# d11toy2ccde.net
KiCad netlist of a schematic drawn in EAGLE
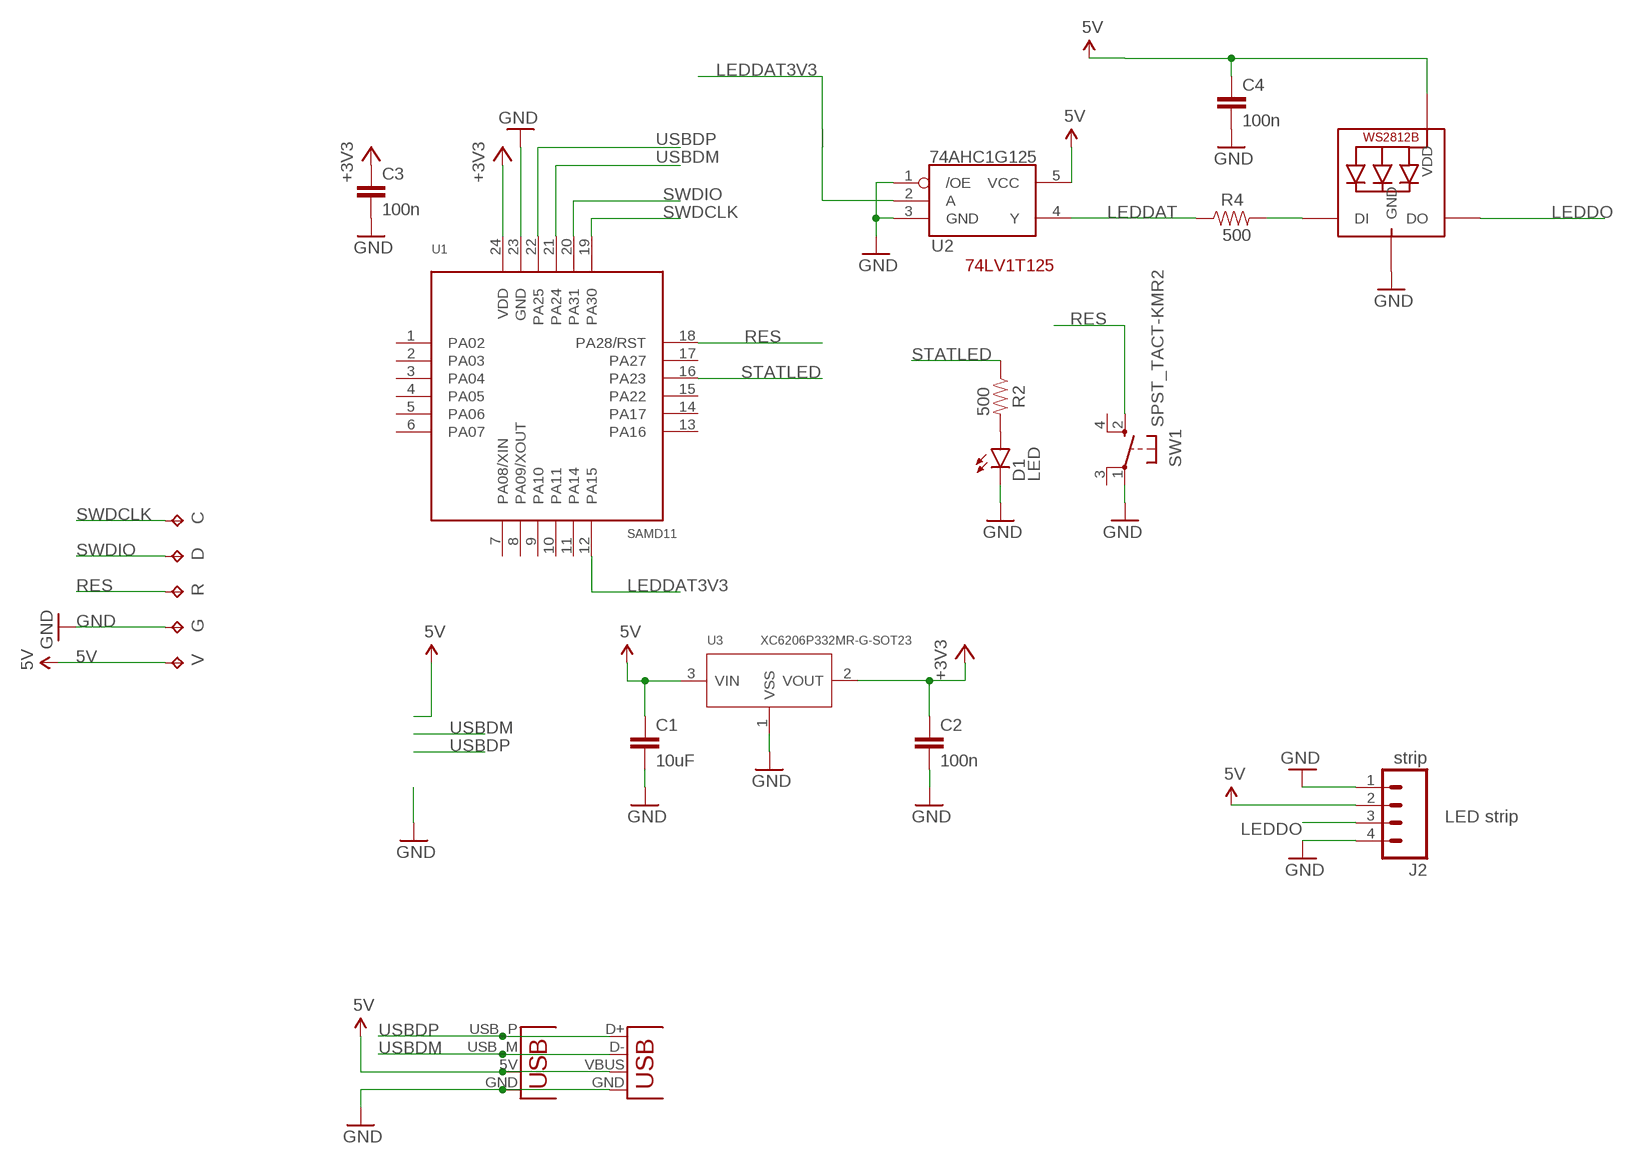
[diagram p0: schematic, sheet 1]

(export (version "E")
  (design (tool "Eeschema 10.0.6"))
  (components
    (comp (ref "C")
      (value "TPTP08R")
      (footprint "eagle-import:TP08R")
      (libsource (lib "eagle-import") (part "TPTP08R"))
    )
    (comp (ref "C1")
      (value "10uF")
      (footprint "eagle-import:0603-CAP")
      (libsource (lib "eagle-import") (part "CAP0603-CAP"))
    )
    (comp (ref "C2")
      (value "100n")
      (footprint "eagle-import:0603-CAP")
      (libsource (lib "eagle-import") (part "CAP0603-CAP"))
    )
    (comp (ref "C3")
      (value "100n")
      (footprint "eagle-import:0603-CAP")
      (libsource (lib "eagle-import") (part "CAP0603-CAP"))
    )
    (comp (ref "C4")
      (value "100n")
      (footprint "eagle-import:0603-CAP")
      (libsource (lib "eagle-import") (part "CAP0603-CAP"))
    )
    (comp (ref "D")
      (value "TPTP08R")
      (footprint "eagle-import:TP08R")
      (libsource (lib "eagle-import") (part "TPTP08R"))
    )
    (comp (ref "D1")
      (value "LED")
      (footprint "eagle-import:LED-0603")
      (libsource (lib "eagle-import") (part "LED0603"))
    )
    (comp (ref "G")
      (value "TPTP08R")
      (footprint "eagle-import:TP08R")
      (libsource (lib "eagle-import") (part "TPTP08R"))
    )
    (comp (ref "J2")
      (value "strip")
      (footprint "eagle-import:1X04_NO_SILK_ALL_ROUND")
      (libsource (lib "eagle-import") (part "M04NO_SILK_ALL_ROUND"))
    )
    (comp (ref "JP1")
      (value "USBPCB")
      (footprint "eagle-import:USB-A-PCB")
      (libsource (lib "eagle-import") (part "USBPCB"))
    )
    (comp (ref "JP3")
      (value "USB-MICROB")
      (footprint "eagle-import:USB-MICROB")
      (libsource (lib "eagle-import") (part "USB-MICROB"))
    )
    (comp (ref "LED1")
      (value "WS2812B5050")
      (footprint "eagle-import:WS2812B")
      (libsource (lib "eagle-import") (part "WS2812B5050"))
    )
    (comp (ref "R")
      (value "TPTP08R")
      (footprint "eagle-import:TP08R")
      (libsource (lib "eagle-import") (part "TPTP08R"))
    )
    (comp (ref "R2")
      (value "500")
      (footprint "eagle-import:0603-RES")
      (libsource (lib "eagle-import") (part "RESISTOR0603-RES"))
    )
    (comp (ref "R4")
      (value "500")
      (footprint "eagle-import:0603-RES")
      (libsource (lib "eagle-import") (part "RESISTOR0603-RES"))
    )
    (comp (ref "SW1")
      (value "SPST_TACT-KMR2")
      (footprint "eagle-import:KMR2")
      (libsource (lib "eagle-import") (part "SPST_TACT-KMR2"))
    )
    (comp (ref "U1")
      (value "SAMD11")
      (footprint "eagle-import:QFN24")
      (libsource (lib "eagle-import") (part "SAMD11D14AM"))
    )
    (comp (ref "U2")
      (value "74AHC1G125")
      (footprint "eagle-import:SOT23-5")
      (libsource (lib "eagle-import") (part "74AHC1G125"))
    )
    (comp (ref "U3")
      (value "XC6206P332MR-G-SOT23")
      (footprint "eagle-import:SOT-23")
      (fields (field (name "MPN") "XC6206P332MR-G"))
      (libsource (lib "eagle-import") (part "PMIC-LDO-XC6206P332MR-G(SOT23)"))
    )
    (comp (ref "V")
      (value "TPTP08R")
      (footprint "eagle-import:TP08R")
      (libsource (lib "eagle-import") (part "TPTP08R"))
    )
  )
  (nets
    (net (code "1") (name "+3V3") (class "Default")
      (node (ref "C2") (pin "1") (pinfunction "1_1") (pintype "passive"))
      (node (ref "C3") (pin "1") (pinfunction "1_1") (pintype "passive"))
      (node (ref "U1") (pin "24") (pinfunction "VDD_24") (pintype "bidirectional"))
      (node (ref "U3") (pin "2") (pinfunction "VOUT_2") (pintype "output"))
    )
    (net (code "2") (name "/LEDDAT") (class "Default")
      (node (ref "R4") (pin "1") (pinfunction "1_1") (pintype "passive"))
      (node (ref "U2") (pin "4") (pinfunction "Y_4") (pintype "bidirectional"))
    )
    (net (code "3") (name "/LEDDAT3V3") (class "Default")
      (node (ref "U1") (pin "12") (pinfunction "PA15_12") (pintype "bidirectional"))
      (node (ref "U2") (pin "2") (pinfunction "A_2") (pintype "bidirectional"))
    )
    (net (code "4") (name "/LEDDO") (class "Default")
      (node (ref "J2") (pin "3") (pinfunction "3_3") (pintype "passive"))
      (node (ref "LED1") (pin "2-DOUT") (pinfunction "DO_2-DOUT") (pintype "output"))
    )
    (net (code "5") (name "/RES") (class "Default")
      (node (ref "R") (pin "TP") (pinfunction "TP_TP") (pintype "input"))
      (node (ref "SW1") (pin "2") (pinfunction "S_2") (pintype "passive"))
      (node (ref "U1") (pin "18") (pinfunction "PA28/RST_18") (pintype "bidirectional"))
    )
    (net (code "6") (name "/STATLED") (class "Default")
      (node (ref "R2") (pin "1") (pinfunction "1_1") (pintype "passive"))
      (node (ref "U1") (pin "16") (pinfunction "PA23_16") (pintype "bidirectional"))
    )
    (net (code "7") (name "/SWDCLK") (class "Default")
      (node (ref "C") (pin "TP") (pinfunction "TP_TP") (pintype "input"))
      (node (ref "U1") (pin "19") (pinfunction "PA30_19") (pintype "bidirectional"))
    )
    (net (code "8") (name "/SWDIO") (class "Default")
      (node (ref "D") (pin "TP") (pinfunction "TP_TP") (pintype "input"))
      (node (ref "U1") (pin "20") (pinfunction "PA31_20") (pintype "bidirectional"))
    )
    (net (code "9") (name "/USBDM") (class "Default")
      (node (ref "JP1") (pin "USB_M") (pinfunction "D-_USB_M") (pintype "bidirectional"))
      (node (ref "JP3") (pin "D-") (pinfunction "D-_D-") (pintype "bidirectional"))
      (node (ref "U1") (pin "21") (pinfunction "PA24_21") (pintype "bidirectional"))
    )
    (net (code "10") (name "/USBDP") (class "Default")
      (node (ref "JP1") (pin "USB_P") (pinfunction "D+_USB_P") (pintype "bidirectional"))
      (node (ref "JP3") (pin "D+") (pinfunction "D+_D+") (pintype "bidirectional"))
      (node (ref "U1") (pin "22") (pinfunction "PA25_22") (pintype "bidirectional"))
    )
    (net (code "11") (name "5V") (class "Default")
      (node (ref "C1") (pin "1") (pinfunction "1_1") (pintype "passive"))
      (node (ref "C4") (pin "1") (pinfunction "1_1") (pintype "passive"))
      (node (ref "J2") (pin "2") (pinfunction "2_2") (pintype "passive"))
      (node (ref "JP1") (pin "5V") (pinfunction "VBUS_5V") (pintype "bidirectional"))
      (node (ref "JP3") (pin "VBUS") (pinfunction "VBUS_VBUS") (pintype "bidirectional"))
      (node (ref "LED1") (pin "1-VDD") (pinfunction "VDD_1-VDD") (pintype "power_in"))
      (node (ref "U2") (pin "5") (pinfunction "VCC_5") (pintype "bidirectional"))
      (node (ref "U3") (pin "3") (pinfunction "VIN_3") (pintype "input"))
      (node (ref "V") (pin "TP") (pinfunction "TP_TP") (pintype "input"))
    )
    (net (code "12") (name "GND") (class "Default")
      (node (ref "C1") (pin "2") (pinfunction "2_2") (pintype "passive"))
      (node (ref "C2") (pin "2") (pinfunction "2_2") (pintype "passive"))
      (node (ref "C3") (pin "2") (pinfunction "2_2") (pintype "passive"))
      (node (ref "C4") (pin "2") (pinfunction "2_2") (pintype "passive"))
      (node (ref "D1") (pin "C") (pinfunction "C_C") (pintype "passive"))
      (node (ref "G") (pin "TP") (pinfunction "TP_TP") (pintype "input"))
      (node (ref "J2") (pin "1") (pinfunction "1_1") (pintype "passive"))
      (node (ref "J2") (pin "4") (pinfunction "4_4") (pintype "passive"))
      (node (ref "JP1") (pin "GND") (pinfunction "GND_GND") (pintype "bidirectional"))
      (node (ref "JP3") (pin "GND") (pinfunction "GND_GND") (pintype "bidirectional"))
      (node (ref "LED1") (pin "3-GND") (pinfunction "GND_3-GND") (pintype "power_in"))
      (node (ref "SW1") (pin "1") (pinfunction "P_1") (pintype "passive"))
      (node (ref "U1") (pin "23") (pinfunction "GND_23") (pintype "bidirectional"))
      (node (ref "U2") (pin "1") (pinfunction "/OE_1") (pintype "bidirectional"))
      (node (ref "U2") (pin "3") (pinfunction "GND_3") (pintype "bidirectional"))
      (node (ref "U3") (pin "1") (pinfunction "VSS_1") (pintype "power_in"))
    )
    (net (code "13") (name "Net-(D1-PadA)") (class "Default")
      (node (ref "D1") (pin "A") (pinfunction "A_A") (pintype "passive"))
      (node (ref "R2") (pin "2") (pinfunction "2_2") (pintype "passive"))
    )
    (net (code "14") (name "Net-(LED1-DI)") (class "Default")
      (node (ref "LED1") (pin "4-DIN") (pinfunction "DI_4-DIN") (pintype "input"))
      (node (ref "R4") (pin "2") (pinfunction "2_2") (pintype "passive"))
    )
    (net (code "15") (name "unconnected-(SW1-P1-Pad3)") (class "Default")
      (node (ref "SW1") (pin "3") (pinfunction "P1_3") (pintype "passive"))
    )
    (net (code "16") (name "unconnected-(SW1-S1-Pad4)") (class "Default")
      (node (ref "SW1") (pin "4") (pinfunction "S1_4") (pintype "passive"))
    )
    (net (code "17") (name "unconnected-(U1-PA02-Pad1)") (class "Default")
      (node (ref "U1") (pin "1") (pinfunction "PA02_1") (pintype "bidirectional"))
    )
    (net (code "18") (name "unconnected-(U1-PA03-Pad2)") (class "Default")
      (node (ref "U1") (pin "2") (pinfunction "PA03_2") (pintype "bidirectional"))
    )
    (net (code "19") (name "unconnected-(U1-PA04-Pad3)") (class "Default")
      (node (ref "U1") (pin "3") (pinfunction "PA04_3") (pintype "bidirectional"))
    )
    (net (code "20") (name "unconnected-(U1-PA05-Pad4)") (class "Default")
      (node (ref "U1") (pin "4") (pinfunction "PA05_4") (pintype "bidirectional"))
    )
    (net (code "21") (name "unconnected-(U1-PA06-Pad5)") (class "Default")
      (node (ref "U1") (pin "5") (pinfunction "PA06_5") (pintype "bidirectional"))
    )
    (net (code "22") (name "unconnected-(U1-PA07-Pad6)") (class "Default")
      (node (ref "U1") (pin "6") (pinfunction "PA07_6") (pintype "bidirectional"))
    )
    (net (code "23") (name "unconnected-(U1-PA08{slash}XIN-Pad7)") (class "Default")
      (node (ref "U1") (pin "7") (pinfunction "PA08/XIN_7") (pintype "bidirectional"))
    )
    (net (code "24") (name "unconnected-(U1-PA09{slash}XOUT-Pad8)") (class "Default")
      (node (ref "U1") (pin "8") (pinfunction "PA09/XOUT_8") (pintype "bidirectional"))
    )
    (net (code "25") (name "unconnected-(U1-PA10-Pad9)") (class "Default")
      (node (ref "U1") (pin "9") (pinfunction "PA10_9") (pintype "bidirectional"))
    )
    (net (code "26") (name "unconnected-(U1-PA11-Pad10)") (class "Default")
      (node (ref "U1") (pin "10") (pinfunction "PA11_10") (pintype "bidirectional"))
    )
    (net (code "27") (name "unconnected-(U1-PA14-Pad11)") (class "Default")
      (node (ref "U1") (pin "11") (pinfunction "PA14_11") (pintype "bidirectional"))
    )
    (net (code "28") (name "unconnected-(U1-PA16-Pad13)") (class "Default")
      (node (ref "U1") (pin "13") (pinfunction "PA16_13") (pintype "bidirectional"))
    )
    (net (code "29") (name "unconnected-(U1-PA17-Pad14)") (class "Default")
      (node (ref "U1") (pin "14") (pinfunction "PA17_14") (pintype "bidirectional"))
    )
    (net (code "30") (name "unconnected-(U1-PA22-Pad15)") (class "Default")
      (node (ref "U1") (pin "15") (pinfunction "PA22_15") (pintype "bidirectional"))
    )
    (net (code "31") (name "unconnected-(U1-PA27-Pad17)") (class "Default")
      (node (ref "U1") (pin "17") (pinfunction "PA27_17") (pintype "bidirectional"))
    )
  )
)
